# panel4.net
KiCad netlist of a schematic drawn in Altium Designer
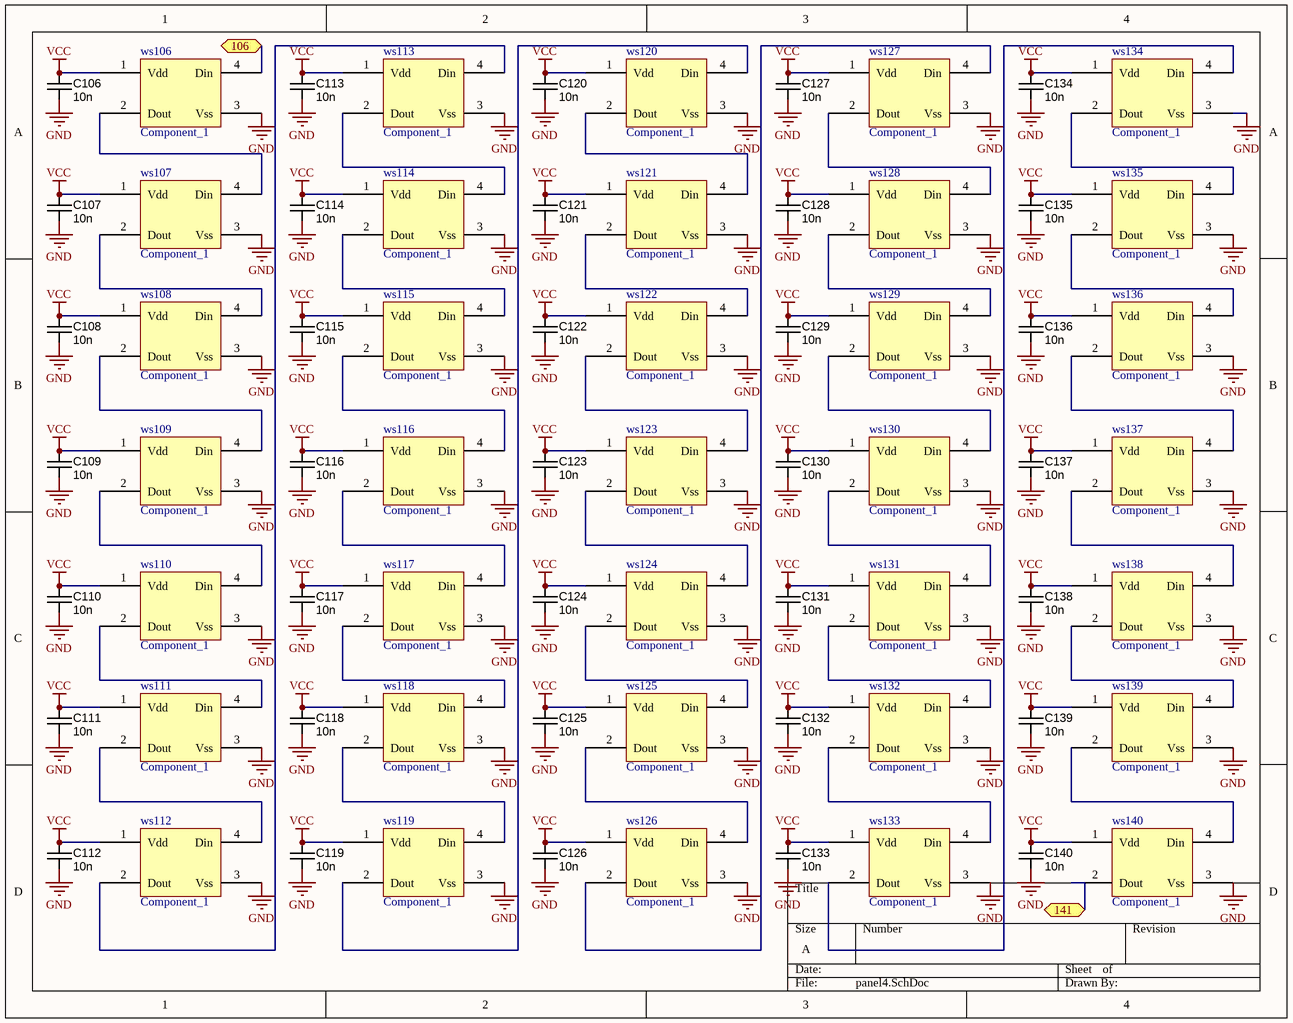
[diagram p0: panel4.SchDoc]

(export (version "E")
  (design (tool "Eeschema 10.0.6"))
  (components
    (comp (ref "C106")
      (value "10n")
      (footprint "CAPC1608X90N")
      (description "Capacitor SMD Cer 10nF 10% 100V X7R 0603")
      (fields
        (field (name "TOLERANCE") "±10%")
        (field (name "MANUFACTURER") "Murata Electronics North America")
      )
      (libsource (lib "PBL - Capacitors") (part "CAPC_10n_0603_X7R_100V_10%"))
    )
    (comp (ref "C107")
      (value "10n")
      (footprint "CAPC1608X90N")
      (description "Capacitor SMD Cer 10nF 10% 100V X7R 0603")
      (fields
        (field (name "TOLERANCE") "±10%")
        (field (name "MANUFACTURER") "Murata Electronics North America")
      )
      (libsource (lib "PBL - Capacitors") (part "CAPC_10n_0603_X7R_100V_10%"))
    )
    (comp (ref "C108")
      (value "10n")
      (footprint "CAPC1608X90N")
      (description "Capacitor SMD Cer 10nF 10% 100V X7R 0603")
      (fields
        (field (name "TOLERANCE") "±10%")
        (field (name "MANUFACTURER") "Murata Electronics North America")
      )
      (libsource (lib "PBL - Capacitors") (part "CAPC_10n_0603_X7R_100V_10%"))
    )
    (comp (ref "C109")
      (value "10n")
      (footprint "CAPC1608X90N")
      (description "Capacitor SMD Cer 10nF 10% 100V X7R 0603")
      (fields
        (field (name "TOLERANCE") "±10%")
        (field (name "MANUFACTURER") "Murata Electronics North America")
      )
      (libsource (lib "PBL - Capacitors") (part "CAPC_10n_0603_X7R_100V_10%"))
    )
    (comp (ref "C110")
      (value "10n")
      (footprint "CAPC1608X90N")
      (description "Capacitor SMD Cer 10nF 10% 100V X7R 0603")
      (fields
        (field (name "TOLERANCE") "±10%")
        (field (name "MANUFACTURER") "Murata Electronics North America")
      )
      (libsource (lib "PBL - Capacitors") (part "CAPC_10n_0603_X7R_100V_10%"))
    )
    (comp (ref "C111")
      (value "10n")
      (footprint "CAPC1608X90N")
      (description "Capacitor SMD Cer 10nF 10% 100V X7R 0603")
      (fields
        (field (name "TOLERANCE") "±10%")
        (field (name "MANUFACTURER") "Murata Electronics North America")
      )
      (libsource (lib "PBL - Capacitors") (part "CAPC_10n_0603_X7R_100V_10%"))
    )
    (comp (ref "C112")
      (value "10n")
      (footprint "CAPC1608X90N")
      (description "Capacitor SMD Cer 10nF 10% 100V X7R 0603")
      (fields
        (field (name "TOLERANCE") "±10%")
        (field (name "MANUFACTURER") "Murata Electronics North America")
      )
      (libsource (lib "PBL - Capacitors") (part "CAPC_10n_0603_X7R_100V_10%"))
    )
    (comp (ref "C113")
      (value "10n")
      (footprint "CAPC1608X90N")
      (description "Capacitor SMD Cer 10nF 10% 100V X7R 0603")
      (fields
        (field (name "TOLERANCE") "±10%")
        (field (name "MANUFACTURER") "Murata Electronics North America")
      )
      (libsource (lib "PBL - Capacitors") (part "CAPC_10n_0603_X7R_100V_10%"))
    )
    (comp (ref "C114")
      (value "10n")
      (footprint "CAPC1608X90N")
      (description "Capacitor SMD Cer 10nF 10% 100V X7R 0603")
      (fields
        (field (name "TOLERANCE") "±10%")
        (field (name "MANUFACTURER") "Murata Electronics North America")
      )
      (libsource (lib "PBL - Capacitors") (part "CAPC_10n_0603_X7R_100V_10%"))
    )
    (comp (ref "C115")
      (value "10n")
      (footprint "CAPC1608X90N")
      (description "Capacitor SMD Cer 10nF 10% 100V X7R 0603")
      (fields
        (field (name "TOLERANCE") "±10%")
        (field (name "MANUFACTURER") "Murata Electronics North America")
      )
      (libsource (lib "PBL - Capacitors") (part "CAPC_10n_0603_X7R_100V_10%"))
    )
    (comp (ref "C116")
      (value "10n")
      (footprint "CAPC1608X90N")
      (description "Capacitor SMD Cer 10nF 10% 100V X7R 0603")
      (fields
        (field (name "TOLERANCE") "±10%")
        (field (name "MANUFACTURER") "Murata Electronics North America")
      )
      (libsource (lib "PBL - Capacitors") (part "CAPC_10n_0603_X7R_100V_10%"))
    )
    (comp (ref "C117")
      (value "10n")
      (footprint "CAPC1608X90N")
      (description "Capacitor SMD Cer 10nF 10% 100V X7R 0603")
      (fields
        (field (name "TOLERANCE") "±10%")
        (field (name "MANUFACTURER") "Murata Electronics North America")
      )
      (libsource (lib "PBL - Capacitors") (part "CAPC_10n_0603_X7R_100V_10%"))
    )
    (comp (ref "C118")
      (value "10n")
      (footprint "CAPC1608X90N")
      (description "Capacitor SMD Cer 10nF 10% 100V X7R 0603")
      (fields
        (field (name "TOLERANCE") "±10%")
        (field (name "MANUFACTURER") "Murata Electronics North America")
      )
      (libsource (lib "PBL - Capacitors") (part "CAPC_10n_0603_X7R_100V_10%"))
    )
    (comp (ref "C119")
      (value "10n")
      (footprint "CAPC1608X90N")
      (description "Capacitor SMD Cer 10nF 10% 100V X7R 0603")
      (fields
        (field (name "TOLERANCE") "±10%")
        (field (name "MANUFACTURER") "Murata Electronics North America")
      )
      (libsource (lib "PBL - Capacitors") (part "CAPC_10n_0603_X7R_100V_10%"))
    )
    (comp (ref "C120")
      (value "10n")
      (footprint "CAPC1608X90N")
      (description "Capacitor SMD Cer 10nF 10% 100V X7R 0603")
      (fields
        (field (name "TOLERANCE") "±10%")
        (field (name "MANUFACTURER") "Murata Electronics North America")
      )
      (libsource (lib "PBL - Capacitors") (part "CAPC_10n_0603_X7R_100V_10%"))
    )
    (comp (ref "C121")
      (value "10n")
      (footprint "CAPC1608X90N")
      (description "Capacitor SMD Cer 10nF 10% 100V X7R 0603")
      (fields
        (field (name "TOLERANCE") "±10%")
        (field (name "MANUFACTURER") "Murata Electronics North America")
      )
      (libsource (lib "PBL - Capacitors") (part "CAPC_10n_0603_X7R_100V_10%"))
    )
    (comp (ref "C122")
      (value "10n")
      (footprint "CAPC1608X90N")
      (description "Capacitor SMD Cer 10nF 10% 100V X7R 0603")
      (fields
        (field (name "TOLERANCE") "±10%")
        (field (name "MANUFACTURER") "Murata Electronics North America")
      )
      (libsource (lib "PBL - Capacitors") (part "CAPC_10n_0603_X7R_100V_10%"))
    )
    (comp (ref "C123")
      (value "10n")
      (footprint "CAPC1608X90N")
      (description "Capacitor SMD Cer 10nF 10% 100V X7R 0603")
      (fields
        (field (name "TOLERANCE") "±10%")
        (field (name "MANUFACTURER") "Murata Electronics North America")
      )
      (libsource (lib "PBL - Capacitors") (part "CAPC_10n_0603_X7R_100V_10%"))
    )
    (comp (ref "C124")
      (value "10n")
      (footprint "CAPC1608X90N")
      (description "Capacitor SMD Cer 10nF 10% 100V X7R 0603")
      (fields
        (field (name "TOLERANCE") "±10%")
        (field (name "MANUFACTURER") "Murata Electronics North America")
      )
      (libsource (lib "PBL - Capacitors") (part "CAPC_10n_0603_X7R_100V_10%"))
    )
    (comp (ref "C125")
      (value "10n")
      (footprint "CAPC1608X90N")
      (description "Capacitor SMD Cer 10nF 10% 100V X7R 0603")
      (fields
        (field (name "TOLERANCE") "±10%")
        (field (name "MANUFACTURER") "Murata Electronics North America")
      )
      (libsource (lib "PBL - Capacitors") (part "CAPC_10n_0603_X7R_100V_10%"))
    )
    (comp (ref "C126")
      (value "10n")
      (footprint "CAPC1608X90N")
      (description "Capacitor SMD Cer 10nF 10% 100V X7R 0603")
      (fields
        (field (name "TOLERANCE") "±10%")
        (field (name "MANUFACTURER") "Murata Electronics North America")
      )
      (libsource (lib "PBL - Capacitors") (part "CAPC_10n_0603_X7R_100V_10%"))
    )
    (comp (ref "C127")
      (value "10n")
      (footprint "CAPC1608X90N")
      (description "Capacitor SMD Cer 10nF 10% 100V X7R 0603")
      (fields
        (field (name "TOLERANCE") "±10%")
        (field (name "MANUFACTURER") "Murata Electronics North America")
      )
      (libsource (lib "PBL - Capacitors") (part "CAPC_10n_0603_X7R_100V_10%"))
    )
    (comp (ref "C128")
      (value "10n")
      (footprint "CAPC1608X90N")
      (description "Capacitor SMD Cer 10nF 10% 100V X7R 0603")
      (fields
        (field (name "TOLERANCE") "±10%")
        (field (name "MANUFACTURER") "Murata Electronics North America")
      )
      (libsource (lib "PBL - Capacitors") (part "CAPC_10n_0603_X7R_100V_10%"))
    )
    (comp (ref "C129")
      (value "10n")
      (footprint "CAPC1608X90N")
      (description "Capacitor SMD Cer 10nF 10% 100V X7R 0603")
      (fields
        (field (name "TOLERANCE") "±10%")
        (field (name "MANUFACTURER") "Murata Electronics North America")
      )
      (libsource (lib "PBL - Capacitors") (part "CAPC_10n_0603_X7R_100V_10%"))
    )
    (comp (ref "C130")
      (value "10n")
      (footprint "CAPC1608X90N")
      (description "Capacitor SMD Cer 10nF 10% 100V X7R 0603")
      (fields
        (field (name "TOLERANCE") "±10%")
        (field (name "MANUFACTURER") "Murata Electronics North America")
      )
      (libsource (lib "PBL - Capacitors") (part "CAPC_10n_0603_X7R_100V_10%"))
    )
    (comp (ref "C131")
      (value "10n")
      (footprint "CAPC1608X90N")
      (description "Capacitor SMD Cer 10nF 10% 100V X7R 0603")
      (fields
        (field (name "TOLERANCE") "±10%")
        (field (name "MANUFACTURER") "Murata Electronics North America")
      )
      (libsource (lib "PBL - Capacitors") (part "CAPC_10n_0603_X7R_100V_10%"))
    )
    (comp (ref "C132")
      (value "10n")
      (footprint "CAPC1608X90N")
      (description "Capacitor SMD Cer 10nF 10% 100V X7R 0603")
      (fields
        (field (name "TOLERANCE") "±10%")
        (field (name "MANUFACTURER") "Murata Electronics North America")
      )
      (libsource (lib "PBL - Capacitors") (part "CAPC_10n_0603_X7R_100V_10%"))
    )
    (comp (ref "C133")
      (value "10n")
      (footprint "CAPC1608X90N")
      (description "Capacitor SMD Cer 10nF 10% 100V X7R 0603")
      (fields
        (field (name "TOLERANCE") "±10%")
        (field (name "MANUFACTURER") "Murata Electronics North America")
      )
      (libsource (lib "PBL - Capacitors") (part "CAPC_10n_0603_X7R_100V_10%"))
    )
    (comp (ref "C134")
      (value "10n")
      (footprint "CAPC1608X90N")
      (description "Capacitor SMD Cer 10nF 10% 100V X7R 0603")
      (fields
        (field (name "TOLERANCE") "±10%")
        (field (name "MANUFACTURER") "Murata Electronics North America")
      )
      (libsource (lib "PBL - Capacitors") (part "CAPC_10n_0603_X7R_100V_10%"))
    )
    (comp (ref "C135")
      (value "10n")
      (footprint "CAPC1608X90N")
      (description "Capacitor SMD Cer 10nF 10% 100V X7R 0603")
      (fields
        (field (name "TOLERANCE") "±10%")
        (field (name "MANUFACTURER") "Murata Electronics North America")
      )
      (libsource (lib "PBL - Capacitors") (part "CAPC_10n_0603_X7R_100V_10%"))
    )
    (comp (ref "C136")
      (value "10n")
      (footprint "CAPC1608X90N")
      (description "Capacitor SMD Cer 10nF 10% 100V X7R 0603")
      (fields
        (field (name "TOLERANCE") "±10%")
        (field (name "MANUFACTURER") "Murata Electronics North America")
      )
      (libsource (lib "PBL - Capacitors") (part "CAPC_10n_0603_X7R_100V_10%"))
    )
    (comp (ref "C137")
      (value "10n")
      (footprint "CAPC1608X90N")
      (description "Capacitor SMD Cer 10nF 10% 100V X7R 0603")
      (fields
        (field (name "TOLERANCE") "±10%")
        (field (name "MANUFACTURER") "Murata Electronics North America")
      )
      (libsource (lib "PBL - Capacitors") (part "CAPC_10n_0603_X7R_100V_10%"))
    )
    (comp (ref "C138")
      (value "10n")
      (footprint "CAPC1608X90N")
      (description "Capacitor SMD Cer 10nF 10% 100V X7R 0603")
      (fields
        (field (name "TOLERANCE") "±10%")
        (field (name "MANUFACTURER") "Murata Electronics North America")
      )
      (libsource (lib "PBL - Capacitors") (part "CAPC_10n_0603_X7R_100V_10%"))
    )
    (comp (ref "C139")
      (value "10n")
      (footprint "CAPC1608X90N")
      (description "Capacitor SMD Cer 10nF 10% 100V X7R 0603")
      (fields
        (field (name "TOLERANCE") "±10%")
        (field (name "MANUFACTURER") "Murata Electronics North America")
      )
      (libsource (lib "PBL - Capacitors") (part "CAPC_10n_0603_X7R_100V_10%"))
    )
    (comp (ref "C140")
      (value "10n")
      (footprint "CAPC1608X90N")
      (description "Capacitor SMD Cer 10nF 10% 100V X7R 0603")
      (fields
        (field (name "TOLERANCE") "±10%")
        (field (name "MANUFACTURER") "Murata Electronics North America")
      )
      (libsource (lib "PBL - Capacitors") (part "CAPC_10n_0603_X7R_100V_10%"))
    )
    (comp (ref "ws106")
      (value "Component_1")
      (footprint "SOP4")
      (libsource (lib "ws2812b") (part "Component_1"))
    )
    (comp (ref "ws107")
      (value "Component_1")
      (footprint "SOP4")
      (libsource (lib "ws2812b") (part "Component_1"))
    )
    (comp (ref "ws108")
      (value "Component_1")
      (footprint "SOP4")
      (libsource (lib "ws2812b") (part "Component_1"))
    )
    (comp (ref "ws109")
      (value "Component_1")
      (footprint "SOP4")
      (libsource (lib "ws2812b") (part "Component_1"))
    )
    (comp (ref "ws110")
      (value "Component_1")
      (footprint "SOP4")
      (libsource (lib "ws2812b") (part "Component_1"))
    )
    (comp (ref "ws111")
      (value "Component_1")
      (footprint "SOP4")
      (libsource (lib "ws2812b") (part "Component_1"))
    )
    (comp (ref "ws112")
      (value "Component_1")
      (footprint "SOP4")
      (libsource (lib "ws2812b") (part "Component_1"))
    )
    (comp (ref "ws113")
      (value "Component_1")
      (footprint "SOP4")
      (libsource (lib "ws2812b") (part "Component_1"))
    )
    (comp (ref "ws114")
      (value "Component_1")
      (footprint "SOP4")
      (libsource (lib "ws2812b") (part "Component_1"))
    )
    (comp (ref "ws115")
      (value "Component_1")
      (footprint "SOP4")
      (libsource (lib "ws2812b") (part "Component_1"))
    )
    (comp (ref "ws116")
      (value "Component_1")
      (footprint "SOP4")
      (libsource (lib "ws2812b") (part "Component_1"))
    )
    (comp (ref "ws117")
      (value "Component_1")
      (footprint "SOP4")
      (libsource (lib "ws2812b") (part "Component_1"))
    )
    (comp (ref "ws118")
      (value "Component_1")
      (footprint "SOP4")
      (libsource (lib "ws2812b") (part "Component_1"))
    )
    (comp (ref "ws119")
      (value "Component_1")
      (footprint "SOP4")
      (libsource (lib "ws2812b") (part "Component_1"))
    )
    (comp (ref "ws120")
      (value "Component_1")
      (footprint "SOP4")
      (libsource (lib "ws2812b") (part "Component_1"))
    )
    (comp (ref "ws121")
      (value "Component_1")
      (footprint "SOP4")
      (libsource (lib "ws2812b") (part "Component_1"))
    )
    (comp (ref "ws122")
      (value "Component_1")
      (footprint "SOP4")
      (libsource (lib "ws2812b") (part "Component_1"))
    )
    (comp (ref "ws123")
      (value "Component_1")
      (footprint "SOP4")
      (libsource (lib "ws2812b") (part "Component_1"))
    )
    (comp (ref "ws124")
      (value "Component_1")
      (footprint "SOP4")
      (libsource (lib "ws2812b") (part "Component_1"))
    )
    (comp (ref "ws125")
      (value "Component_1")
      (footprint "SOP4")
      (libsource (lib "ws2812b") (part "Component_1"))
    )
    (comp (ref "ws126")
      (value "Component_1")
      (footprint "SOP4")
      (libsource (lib "ws2812b") (part "Component_1"))
    )
    (comp (ref "ws127")
      (value "Component_1")
      (footprint "SOP4")
      (libsource (lib "ws2812b") (part "Component_1"))
    )
    (comp (ref "ws128")
      (value "Component_1")
      (footprint "SOP4")
      (libsource (lib "ws2812b") (part "Component_1"))
    )
    (comp (ref "ws129")
      (value "Component_1")
      (footprint "SOP4")
      (libsource (lib "ws2812b") (part "Component_1"))
    )
    (comp (ref "ws130")
      (value "Component_1")
      (footprint "SOP4")
      (libsource (lib "ws2812b") (part "Component_1"))
    )
    (comp (ref "ws131")
      (value "Component_1")
      (footprint "SOP4")
      (libsource (lib "ws2812b") (part "Component_1"))
    )
    (comp (ref "ws132")
      (value "Component_1")
      (footprint "SOP4")
      (libsource (lib "ws2812b") (part "Component_1"))
    )
    (comp (ref "ws133")
      (value "Component_1")
      (footprint "SOP4")
      (libsource (lib "ws2812b") (part "Component_1"))
    )
    (comp (ref "ws134")
      (value "Component_1")
      (footprint "SOP4")
      (libsource (lib "ws2812b") (part "Component_1"))
    )
    (comp (ref "ws135")
      (value "Component_1")
      (footprint "SOP4")
      (libsource (lib "ws2812b") (part "Component_1"))
    )
    (comp (ref "ws136")
      (value "Component_1")
      (footprint "SOP4")
      (libsource (lib "ws2812b") (part "Component_1"))
    )
    (comp (ref "ws137")
      (value "Component_1")
      (footprint "SOP4")
      (libsource (lib "ws2812b") (part "Component_1"))
    )
    (comp (ref "ws138")
      (value "Component_1")
      (footprint "SOP4")
      (libsource (lib "ws2812b") (part "Component_1"))
    )
    (comp (ref "ws139")
      (value "Component_1")
      (footprint "SOP4")
      (libsource (lib "ws2812b") (part "Component_1"))
    )
    (comp (ref "ws140")
      (value "Component_1")
      (footprint "SOP4")
      (libsource (lib "ws2812b") (part "Component_1"))
    )
  )
  (nets
    (net (code "1") (name "/106") (class "Default")
      (node (ref "ws106") (pin "4") (pinfunction "Din_4") (pintype "passive"))
    )
    (net (code "2") (name "/141") (class "Default")
      (node (ref "ws140") (pin "2") (pinfunction "Dout_2") (pintype "passive"))
    )
    (net (code "3") (name "GND") (class "Default")
      (node (ref "C106") (pin "2") (pintype "passive"))
      (node (ref "C107") (pin "2") (pintype "passive"))
      (node (ref "C108") (pin "2") (pintype "passive"))
      (node (ref "C109") (pin "2") (pintype "passive"))
      (node (ref "C110") (pin "2") (pintype "passive"))
      (node (ref "C111") (pin "2") (pintype "passive"))
      (node (ref "C112") (pin "2") (pintype "passive"))
      (node (ref "C113") (pin "2") (pintype "passive"))
      (node (ref "C114") (pin "2") (pintype "passive"))
      (node (ref "C115") (pin "2") (pintype "passive"))
      (node (ref "C116") (pin "2") (pintype "passive"))
      (node (ref "C117") (pin "2") (pintype "passive"))
      (node (ref "C118") (pin "2") (pintype "passive"))
      (node (ref "C119") (pin "2") (pintype "passive"))
      (node (ref "C120") (pin "2") (pintype "passive"))
      (node (ref "C121") (pin "2") (pintype "passive"))
      (node (ref "C122") (pin "2") (pintype "passive"))
      (node (ref "C123") (pin "2") (pintype "passive"))
      (node (ref "C124") (pin "2") (pintype "passive"))
      (node (ref "C125") (pin "2") (pintype "passive"))
      (node (ref "C126") (pin "2") (pintype "passive"))
      (node (ref "C127") (pin "2") (pintype "passive"))
      (node (ref "C128") (pin "2") (pintype "passive"))
      (node (ref "C129") (pin "2") (pintype "passive"))
      (node (ref "C130") (pin "2") (pintype "passive"))
      (node (ref "C131") (pin "2") (pintype "passive"))
      (node (ref "C132") (pin "2") (pintype "passive"))
      (node (ref "C133") (pin "2") (pintype "passive"))
      (node (ref "C134") (pin "2") (pintype "passive"))
      (node (ref "C135") (pin "2") (pintype "passive"))
      (node (ref "C136") (pin "2") (pintype "passive"))
      (node (ref "C137") (pin "2") (pintype "passive"))
      (node (ref "C138") (pin "2") (pintype "passive"))
      (node (ref "C139") (pin "2") (pintype "passive"))
      (node (ref "C140") (pin "2") (pintype "passive"))
      (node (ref "ws106") (pin "3") (pinfunction "Vss_3") (pintype "passive"))
      (node (ref "ws107") (pin "3") (pinfunction "Vss_3") (pintype "passive"))
      (node (ref "ws108") (pin "3") (pinfunction "Vss_3") (pintype "passive"))
      (node (ref "ws109") (pin "3") (pinfunction "Vss_3") (pintype "passive"))
      (node (ref "ws110") (pin "3") (pinfunction "Vss_3") (pintype "passive"))
      (node (ref "ws111") (pin "3") (pinfunction "Vss_3") (pintype "passive"))
      (node (ref "ws112") (pin "3") (pinfunction "Vss_3") (pintype "passive"))
      (node (ref "ws113") (pin "3") (pinfunction "Vss_3") (pintype "passive"))
      (node (ref "ws114") (pin "3") (pinfunction "Vss_3") (pintype "passive"))
      (node (ref "ws115") (pin "3") (pinfunction "Vss_3") (pintype "passive"))
      (node (ref "ws116") (pin "3") (pinfunction "Vss_3") (pintype "passive"))
      (node (ref "ws117") (pin "3") (pinfunction "Vss_3") (pintype "passive"))
      (node (ref "ws118") (pin "3") (pinfunction "Vss_3") (pintype "passive"))
      (node (ref "ws119") (pin "3") (pinfunction "Vss_3") (pintype "passive"))
      (node (ref "ws120") (pin "3") (pinfunction "Vss_3") (pintype "passive"))
      (node (ref "ws121") (pin "3") (pinfunction "Vss_3") (pintype "passive"))
      (node (ref "ws122") (pin "3") (pinfunction "Vss_3") (pintype "passive"))
      (node (ref "ws123") (pin "3") (pinfunction "Vss_3") (pintype "passive"))
      (node (ref "ws124") (pin "3") (pinfunction "Vss_3") (pintype "passive"))
      (node (ref "ws125") (pin "3") (pinfunction "Vss_3") (pintype "passive"))
      (node (ref "ws126") (pin "3") (pinfunction "Vss_3") (pintype "passive"))
      (node (ref "ws127") (pin "3") (pinfunction "Vss_3") (pintype "passive"))
      (node (ref "ws128") (pin "3") (pinfunction "Vss_3") (pintype "passive"))
      (node (ref "ws129") (pin "3") (pinfunction "Vss_3") (pintype "passive"))
      (node (ref "ws130") (pin "3") (pinfunction "Vss_3") (pintype "passive"))
      (node (ref "ws131") (pin "3") (pinfunction "Vss_3") (pintype "passive"))
      (node (ref "ws132") (pin "3") (pinfunction "Vss_3") (pintype "passive"))
      (node (ref "ws133") (pin "3") (pinfunction "Vss_3") (pintype "passive"))
      (node (ref "ws134") (pin "3") (pinfunction "Vss_3") (pintype "passive"))
      (node (ref "ws135") (pin "3") (pinfunction "Vss_3") (pintype "passive"))
      (node (ref "ws136") (pin "3") (pinfunction "Vss_3") (pintype "passive"))
      (node (ref "ws137") (pin "3") (pinfunction "Vss_3") (pintype "passive"))
      (node (ref "ws138") (pin "3") (pinfunction "Vss_3") (pintype "passive"))
      (node (ref "ws139") (pin "3") (pinfunction "Vss_3") (pintype "passive"))
      (node (ref "ws140") (pin "3") (pinfunction "Vss_3") (pintype "passive"))
    )
    (net (code "4") (name "Net-(ws106-Dout)") (class "Default")
      (node (ref "ws106") (pin "2") (pinfunction "Dout_2") (pintype "passive"))
      (node (ref "ws107") (pin "4") (pinfunction "Din_4") (pintype "passive"))
    )
    (net (code "5") (name "Net-(ws107-Dout)") (class "Default")
      (node (ref "ws107") (pin "2") (pinfunction "Dout_2") (pintype "passive"))
      (node (ref "ws108") (pin "4") (pinfunction "Din_4") (pintype "passive"))
    )
    (net (code "6") (name "Net-(ws108-Dout)") (class "Default")
      (node (ref "ws108") (pin "2") (pinfunction "Dout_2") (pintype "passive"))
      (node (ref "ws109") (pin "4") (pinfunction "Din_4") (pintype "passive"))
    )
    (net (code "7") (name "Net-(ws109-Dout)") (class "Default")
      (node (ref "ws109") (pin "2") (pinfunction "Dout_2") (pintype "passive"))
      (node (ref "ws110") (pin "4") (pinfunction "Din_4") (pintype "passive"))
    )
    (net (code "8") (name "Net-(ws110-Dout)") (class "Default")
      (node (ref "ws110") (pin "2") (pinfunction "Dout_2") (pintype "passive"))
      (node (ref "ws111") (pin "4") (pinfunction "Din_4") (pintype "passive"))
    )
    (net (code "9") (name "Net-(ws111-Dout)") (class "Default")
      (node (ref "ws111") (pin "2") (pinfunction "Dout_2") (pintype "passive"))
      (node (ref "ws112") (pin "4") (pinfunction "Din_4") (pintype "passive"))
    )
    (net (code "10") (name "Net-(ws112-Dout)") (class "Default")
      (node (ref "ws112") (pin "2") (pinfunction "Dout_2") (pintype "passive"))
      (node (ref "ws113") (pin "4") (pinfunction "Din_4") (pintype "passive"))
    )
    (net (code "11") (name "Net-(ws113-Dout)") (class "Default")
      (node (ref "ws113") (pin "2") (pinfunction "Dout_2") (pintype "passive"))
      (node (ref "ws114") (pin "4") (pinfunction "Din_4") (pintype "passive"))
    )
    (net (code "12") (name "Net-(ws114-Dout)") (class "Default")
      (node (ref "ws114") (pin "2") (pinfunction "Dout_2") (pintype "passive"))
      (node (ref "ws115") (pin "4") (pinfunction "Din_4") (pintype "passive"))
    )
    (net (code "13") (name "Net-(ws115-Dout)") (class "Default")
      (node (ref "ws115") (pin "2") (pinfunction "Dout_2") (pintype "passive"))
      (node (ref "ws116") (pin "4") (pinfunction "Din_4") (pintype "passive"))
    )
    (net (code "14") (name "Net-(ws116-Dout)") (class "Default")
      (node (ref "ws116") (pin "2") (pinfunction "Dout_2") (pintype "passive"))
      (node (ref "ws117") (pin "4") (pinfunction "Din_4") (pintype "passive"))
    )
    (net (code "15") (name "Net-(ws117-Dout)") (class "Default")
      (node (ref "ws117") (pin "2") (pinfunction "Dout_2") (pintype "passive"))
      (node (ref "ws118") (pin "4") (pinfunction "Din_4") (pintype "passive"))
    )
    (net (code "16") (name "Net-(ws118-Dout)") (class "Default")
      (node (ref "ws118") (pin "2") (pinfunction "Dout_2") (pintype "passive"))
      (node (ref "ws119") (pin "4") (pinfunction "Din_4") (pintype "passive"))
    )
    (net (code "17") (name "Net-(ws119-Dout)") (class "Default")
      (node (ref "ws119") (pin "2") (pinfunction "Dout_2") (pintype "passive"))
      (node (ref "ws120") (pin "4") (pinfunction "Din_4") (pintype "passive"))
    )
    (net (code "18") (name "Net-(ws120-Dout)") (class "Default")
      (node (ref "ws120") (pin "2") (pinfunction "Dout_2") (pintype "passive"))
      (node (ref "ws121") (pin "4") (pinfunction "Din_4") (pintype "passive"))
    )
    (net (code "19") (name "Net-(ws121-Dout)") (class "Default")
      (node (ref "ws121") (pin "2") (pinfunction "Dout_2") (pintype "passive"))
      (node (ref "ws122") (pin "4") (pinfunction "Din_4") (pintype "passive"))
    )
    (net (code "20") (name "Net-(ws122-Dout)") (class "Default")
      (node (ref "ws122") (pin "2") (pinfunction "Dout_2") (pintype "passive"))
      (node (ref "ws123") (pin "4") (pinfunction "Din_4") (pintype "passive"))
    )
    (net (code "21") (name "Net-(ws123-Dout)") (class "Default")
      (node (ref "ws123") (pin "2") (pinfunction "Dout_2") (pintype "passive"))
      (node (ref "ws124") (pin "4") (pinfunction "Din_4") (pintype "passive"))
    )
    (net (code "22") (name "Net-(ws124-Dout)") (class "Default")
      (node (ref "ws124") (pin "2") (pinfunction "Dout_2") (pintype "passive"))
      (node (ref "ws125") (pin "4") (pinfunction "Din_4") (pintype "passive"))
    )
    (net (code "23") (name "Net-(ws125-Dout)") (class "Default")
      (node (ref "ws125") (pin "2") (pinfunction "Dout_2") (pintype "passive"))
      (node (ref "ws126") (pin "4") (pinfunction "Din_4") (pintype "passive"))
    )
    (net (code "24") (name "Net-(ws126-Dout)") (class "Default")
      (node (ref "ws126") (pin "2") (pinfunction "Dout_2") (pintype "passive"))
      (node (ref "ws127") (pin "4") (pinfunction "Din_4") (pintype "passive"))
    )
    (net (code "25") (name "Net-(ws127-Dout)") (class "Default")
      (node (ref "ws127") (pin "2") (pinfunction "Dout_2") (pintype "passive"))
      (node (ref "ws128") (pin "4") (pinfunction "Din_4") (pintype "passive"))
    )
    (net (code "26") (name "Net-(ws128-Dout)") (class "Default")
      (node (ref "ws128") (pin "2") (pinfunction "Dout_2") (pintype "passive"))
      (node (ref "ws129") (pin "4") (pinfunction "Din_4") (pintype "passive"))
    )
    (net (code "27") (name "Net-(ws129-Dout)") (class "Default")
      (node (ref "ws129") (pin "2") (pinfunction "Dout_2") (pintype "passive"))
      (node (ref "ws130") (pin "4") (pinfunction "Din_4") (pintype "passive"))
    )
    (net (code "28") (name "Net-(ws130-Dout)") (class "Default")
      (node (ref "ws130") (pin "2") (pinfunction "Dout_2") (pintype "passive"))
      (node (ref "ws131") (pin "4") (pinfunction "Din_4") (pintype "passive"))
    )
    (net (code "29") (name "Net-(ws131-Dout)") (class "Default")
      (node (ref "ws131") (pin "2") (pinfunction "Dout_2") (pintype "passive"))
      (node (ref "ws132") (pin "4") (pinfunction "Din_4") (pintype "passive"))
    )
    (net (code "30") (name "Net-(ws132-Dout)") (class "Default")
      (node (ref "ws132") (pin "2") (pinfunction "Dout_2") (pintype "passive"))
      (node (ref "ws133") (pin "4") (pinfunction "Din_4") (pintype "passive"))
    )
    (net (code "31") (name "Net-(ws133-Dout)") (class "Default")
      (node (ref "ws133") (pin "2") (pinfunction "Dout_2") (pintype "passive"))
      (node (ref "ws134") (pin "4") (pinfunction "Din_4") (pintype "passive"))
    )
    (net (code "32") (name "Net-(ws134-Dout)") (class "Default")
      (node (ref "ws134") (pin "2") (pinfunction "Dout_2") (pintype "passive"))
      (node (ref "ws135") (pin "4") (pinfunction "Din_4") (pintype "passive"))
    )
    (net (code "33") (name "Net-(ws135-Dout)") (class "Default")
      (node (ref "ws135") (pin "2") (pinfunction "Dout_2") (pintype "passive"))
      (node (ref "ws136") (pin "4") (pinfunction "Din_4") (pintype "passive"))
    )
    (net (code "34") (name "Net-(ws136-Dout)") (class "Default")
      (node (ref "ws136") (pin "2") (pinfunction "Dout_2") (pintype "passive"))
      (node (ref "ws137") (pin "4") (pinfunction "Din_4") (pintype "passive"))
    )
    (net (code "35") (name "Net-(ws137-Dout)") (class "Default")
      (node (ref "ws137") (pin "2") (pinfunction "Dout_2") (pintype "passive"))
      (node (ref "ws138") (pin "4") (pinfunction "Din_4") (pintype "passive"))
    )
    (net (code "36") (name "Net-(ws138-Dout)") (class "Default")
      (node (ref "ws138") (pin "2") (pinfunction "Dout_2") (pintype "passive"))
      (node (ref "ws139") (pin "4") (pinfunction "Din_4") (pintype "passive"))
    )
    (net (code "37") (name "Net-(ws139-Dout)") (class "Default")
      (node (ref "ws139") (pin "2") (pinfunction "Dout_2") (pintype "passive"))
      (node (ref "ws140") (pin "4") (pinfunction "Din_4") (pintype "passive"))
    )
    (net (code "38") (name "VCC") (class "Default")
      (node (ref "C106") (pin "1") (pintype "passive"))
      (node (ref "C107") (pin "1") (pintype "passive"))
      (node (ref "C108") (pin "1") (pintype "passive"))
      (node (ref "C109") (pin "1") (pintype "passive"))
      (node (ref "C110") (pin "1") (pintype "passive"))
      (node (ref "C111") (pin "1") (pintype "passive"))
      (node (ref "C112") (pin "1") (pintype "passive"))
      (node (ref "C113") (pin "1") (pintype "passive"))
      (node (ref "C114") (pin "1") (pintype "passive"))
      (node (ref "C115") (pin "1") (pintype "passive"))
      (node (ref "C116") (pin "1") (pintype "passive"))
      (node (ref "C117") (pin "1") (pintype "passive"))
      (node (ref "C118") (pin "1") (pintype "passive"))
      (node (ref "C119") (pin "1") (pintype "passive"))
      (node (ref "C120") (pin "1") (pintype "passive"))
      (node (ref "C121") (pin "1") (pintype "passive"))
      (node (ref "C122") (pin "1") (pintype "passive"))
      (node (ref "C123") (pin "1") (pintype "passive"))
      (node (ref "C124") (pin "1") (pintype "passive"))
      (node (ref "C125") (pin "1") (pintype "passive"))
      (node (ref "C126") (pin "1") (pintype "passive"))
      (node (ref "C127") (pin "1") (pintype "passive"))
      (node (ref "C128") (pin "1") (pintype "passive"))
      (node (ref "C129") (pin "1") (pintype "passive"))
      (node (ref "C130") (pin "1") (pintype "passive"))
      (node (ref "C131") (pin "1") (pintype "passive"))
      (node (ref "C132") (pin "1") (pintype "passive"))
      (node (ref "C133") (pin "1") (pintype "passive"))
      (node (ref "C134") (pin "1") (pintype "passive"))
      (node (ref "C135") (pin "1") (pintype "passive"))
      (node (ref "C136") (pin "1") (pintype "passive"))
      (node (ref "C137") (pin "1") (pintype "passive"))
      (node (ref "C138") (pin "1") (pintype "passive"))
      (node (ref "C139") (pin "1") (pintype "passive"))
      (node (ref "C140") (pin "1") (pintype "passive"))
      (node (ref "ws106") (pin "1") (pinfunction "Vdd_1") (pintype "passive"))
      (node (ref "ws107") (pin "1") (pinfunction "Vdd_1") (pintype "passive"))
      (node (ref "ws108") (pin "1") (pinfunction "Vdd_1") (pintype "passive"))
      (node (ref "ws109") (pin "1") (pinfunction "Vdd_1") (pintype "passive"))
      (node (ref "ws110") (pin "1") (pinfunction "Vdd_1") (pintype "passive"))
      (node (ref "ws111") (pin "1") (pinfunction "Vdd_1") (pintype "passive"))
      (node (ref "ws112") (pin "1") (pinfunction "Vdd_1") (pintype "passive"))
      (node (ref "ws113") (pin "1") (pinfunction "Vdd_1") (pintype "passive"))
      (node (ref "ws114") (pin "1") (pinfunction "Vdd_1") (pintype "passive"))
      (node (ref "ws115") (pin "1") (pinfunction "Vdd_1") (pintype "passive"))
      (node (ref "ws116") (pin "1") (pinfunction "Vdd_1") (pintype "passive"))
      (node (ref "ws117") (pin "1") (pinfunction "Vdd_1") (pintype "passive"))
      (node (ref "ws118") (pin "1") (pinfunction "Vdd_1") (pintype "passive"))
      (node (ref "ws119") (pin "1") (pinfunction "Vdd_1") (pintype "passive"))
      (node (ref "ws120") (pin "1") (pinfunction "Vdd_1") (pintype "passive"))
      (node (ref "ws121") (pin "1") (pinfunction "Vdd_1") (pintype "passive"))
      (node (ref "ws122") (pin "1") (pinfunction "Vdd_1") (pintype "passive"))
      (node (ref "ws123") (pin "1") (pinfunction "Vdd_1") (pintype "passive"))
      (node (ref "ws124") (pin "1") (pinfunction "Vdd_1") (pintype "passive"))
      (node (ref "ws125") (pin "1") (pinfunction "Vdd_1") (pintype "passive"))
      (node (ref "ws126") (pin "1") (pinfunction "Vdd_1") (pintype "passive"))
      (node (ref "ws127") (pin "1") (pinfunction "Vdd_1") (pintype "passive"))
      (node (ref "ws128") (pin "1") (pinfunction "Vdd_1") (pintype "passive"))
      (node (ref "ws129") (pin "1") (pinfunction "Vdd_1") (pintype "passive"))
      (node (ref "ws130") (pin "1") (pinfunction "Vdd_1") (pintype "passive"))
      (node (ref "ws131") (pin "1") (pinfunction "Vdd_1") (pintype "passive"))
      (node (ref "ws132") (pin "1") (pinfunction "Vdd_1") (pintype "passive"))
      (node (ref "ws133") (pin "1") (pinfunction "Vdd_1") (pintype "passive"))
      (node (ref "ws134") (pin "1") (pinfunction "Vdd_1") (pintype "passive"))
      (node (ref "ws135") (pin "1") (pinfunction "Vdd_1") (pintype "passive"))
      (node (ref "ws136") (pin "1") (pinfunction "Vdd_1") (pintype "passive"))
      (node (ref "ws137") (pin "1") (pinfunction "Vdd_1") (pintype "passive"))
      (node (ref "ws138") (pin "1") (pinfunction "Vdd_1") (pintype "passive"))
      (node (ref "ws139") (pin "1") (pinfunction "Vdd_1") (pintype "passive"))
      (node (ref "ws140") (pin "1") (pinfunction "Vdd_1") (pintype "passive"))
    )
  )
)
